# DC-DC_24V_To_5V0.net
KiCad netlist of a schematic drawn in Altium Designer
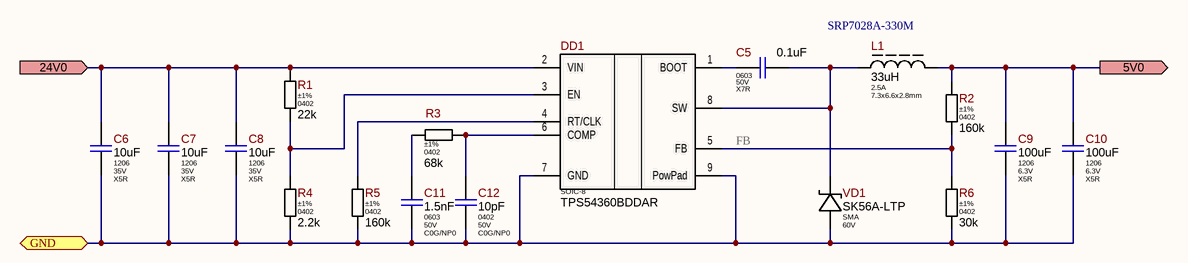
[diagram p0: DC-DC_24V_To_5V0.SchDoc]

(export (version "E")
  (design (tool "Eeschema 10.0.6"))
  (components
    (comp (ref "C5")
      (value "0.1uF")
      (footprint "C_CERAMIC_0603_MED")
      (description "100nF 50V X7R ±10% 0603 Ceramic Capacitor RoHS")
      (fields
        (field (name "PACKAGE") "0603")
        (field (name "VOLTAGE") "50V")
        (field (name "DIELECTRIC TYPE") "X7R")
        (field (name "PART NUMBER") "CL10B104KB8NNNC")
        (field (name "MANUFACTURER") "Samsung Electro-Mechanics")
      )
      (libsource (lib "EL.CVCM.T01") (part "Capacitor-NonPolar"))
    )
    (comp (ref "C6")
      (value "10uF")
      (footprint "CAP-1206(3216)X85T15")
      (description "10uF 35V X5R ±10% 1206 Ceramic Capacitor RoHS")
      (fields
        (field (name "PACKAGE") "1206")
        (field (name "VOLTAGE") "35V")
        (field (name "DIELECTRIC TYPE") "X5R")
        (field (name "PART NUMBER") "GRM319R6YA106KA12D")
        (field (name "MANUFACTURER") "Murata Electronics")
      )
      (libsource (lib "EL.CVCM.T01") (part "Capacitor-NonPolar"))
    )
    (comp (ref "C7")
      (value "10uF")
      (footprint "CAP-1206(3216)X85T15")
      (description "10uF 35V X5R ±10% 1206 Ceramic Capacitor RoHS")
      (fields
        (field (name "PACKAGE") "1206")
        (field (name "VOLTAGE") "35V")
        (field (name "DIELECTRIC TYPE") "X5R")
        (field (name "PART NUMBER") "GRM319R6YA106KA12D")
        (field (name "MANUFACTURER") "Murata Electronics")
      )
      (libsource (lib "EL.CVCM.T01") (part "Capacitor-NonPolar"))
    )
    (comp (ref "C8")
      (value "10uF")
      (footprint "CAP-1206(3216)X85T15")
      (description "10uF 35V X5R ±10% 1206 Ceramic Capacitor RoHS")
      (fields
        (field (name "PACKAGE") "1206")
        (field (name "VOLTAGE") "35V")
        (field (name "DIELECTRIC TYPE") "X5R")
        (field (name "PART NUMBER") "GRM319R6YA106KA12D")
        (field (name "MANUFACTURER") "Murata Electronics")
      )
      (libsource (lib "EL.CVCM.T01") (part "Capacitor-NonPolar"))
    )
    (comp (ref "C9")
      (value "100uF")
      (footprint "C_CERAMIC_1206_MED")
      (description "100uF 6.3V X5R ±20% 1206 Ceramic Capacitor RoHS")
      (fields
        (field (name "PACKAGE") "1206")
        (field (name "VOLTAGE") "6.3V")
        (field (name "DIELECTRIC TYPE") "X5R")
        (field (name "PART NUMBER") "CL31A107MQHNNNE")
        (field (name "MANUFACTURER") "Samsung Electro-Mechanics")
      )
      (libsource (lib "EL.CVCM.T01") (part "Capacitor-NonPolar"))
    )
    (comp (ref "C10")
      (value "100uF")
      (footprint "C_CERAMIC_1206_MED")
      (description "100uF 6.3V X5R ±20% 1206 Ceramic Capacitor RoHS")
      (fields
        (field (name "PACKAGE") "1206")
        (field (name "VOLTAGE") "6.3V")
        (field (name "DIELECTRIC TYPE") "X5R")
        (field (name "PART NUMBER") "CL31A107MQHNNNE")
        (field (name "MANUFACTURER") "Samsung Electro-Mechanics")
      )
      (libsource (lib "EL.CVCM.T01") (part "Capacitor-NonPolar"))
    )
    (comp (ref "C11")
      (value "1.5nF")
      (footprint "C_CERAMIC_0603_MED")
      (description "1.5nF 50V C0G(NP0) ±5% 0603 Ceramic Capacitor RoHS")
      (fields
        (field (name "PACKAGE") "0603")
        (field (name "VOLTAGE") "50V")
        (field (name "DIELECTRIC TYPE") "C0G/NP0")
        (field (name "PART NUMBER") "GRM1885C1H152JA01D")
        (field (name "MANUFACTURER") "Murata Electronics")
      )
      (libsource (lib "EL.CVCM.T01") (part "Capacitor-NonPolar"))
    )
    (comp (ref "C12")
      (value "10pF")
      (footprint "C_CERAMIC_0402_MED")
      (description "10pF 50V C0G ±5% 0402 Ceramic Capacitor RoHS")
      (fields
        (field (name "PACKAGE") "0402")
        (field (name "VOLTAGE") "50V")
        (field (name "DIELECTRIC TYPE") "C0G/NP0")
        (field (name "PART NUMBER") "CL05C100JB5NNNC")
        (field (name "MANUFACTURER") "Samsung Electro-Mechanics")
      )
      (libsource (lib "EL.CVCM.T01") (part "Capacitor-NonPolar"))
    )
    (comp (ref "DD1")
      (value "TPS54360BDDAR")
      (footprint "SOIC127P620X170_HS-9N")
      (description "60V Input, 3.5A, Step-Down DC/DC Converter With Eco-Mode, SOIC-8 EP")
      (fields
        (field (name "PACKAGE") "SOIC-8")
        (field (name "PART NUMBER") "TPS54360BDDAR")
        (field (name "MANUFACTURER") "Texas Instruments")
      )
      (libsource (lib "EL.CVCM.T01") (part "TPS54360B"))
    )
    (comp (ref "L1")
      (value "33uH")
      (footprint "SRP7028A-Series")
      (description "33uH Shielded Wirewound Power Inductor 2.5A 240mOhm Max")
      (fields
        (field (name "CURRENT") "2.5A")
        (field (name "PACKAGE") "7.3x6.6x2.8mm")
        (field (name "PART NUMBER") "SRP7028A-330M")
        (field (name "TOLERANCE") "±20%")
        (field (name "MANUFACTURER") "Bourns Inc")
      )
      (libsource (lib "EL.CVCM.T01") (part "Inductor-Ferrite-Fixed"))
    )
    (comp (ref "R1")
      (value "22k")
      (footprint "R_ANY_CHIP_0402_MED")
      (description "22 kOhms ±1% 1/16W 0402 Thick Film Resistor")
      (fields
        (field (name "TOLERANCE") "±1%")
        (field (name "PACKAGE") "0402")
        (field (name "PART NUMBER") "RC0402FR-0722KL")
        (field (name "MANUFACTURER") "Yageo")
      )
      (libsource (lib "EL.CVCM.T01") (part "Resistor"))
    )
    (comp (ref "R2")
      (value "160k")
      (footprint "R_ANY_CHIP_0402_MED")
      (description "160 kOhms ±1% 1/16W 0402 Thick Film Resistor")
      (fields
        (field (name "TOLERANCE") "±1%")
        (field (name "PACKAGE") "0402")
        (field (name "PART NUMBER") "RC0402FR-07160KL")
        (field (name "MANUFACTURER") "Yageo")
      )
      (libsource (lib "EL.CVCM.T01") (part "Resistor"))
    )
    (comp (ref "R3")
      (value "68k")
      (footprint "R_ANY_CHIP_0402_MED")
      (description "68 kOhms ±1% 1/16W 0402 Thick Film Resistor")
      (fields
        (field (name "TOLERANCE") "±1%")
        (field (name "PACKAGE") "0402")
        (field (name "PART NUMBER") "RC0402FR-0768KL")
        (field (name "MANUFACTURER") "Yageo")
      )
      (libsource (lib "EL.CVCM.T01") (part "Resistor"))
    )
    (comp (ref "R4")
      (value "2.2k")
      (footprint "R_ANY_CHIP_0402_MED")
      (description "2.2 kOhms ±1% 1/16W 0402 Thick Film Resistor")
      (fields
        (field (name "TOLERANCE") "±1%")
        (field (name "PACKAGE") "0402")
        (field (name "PART NUMBER") "RC0402FR-072K2L")
        (field (name "MANUFACTURER") "Yageo")
      )
      (libsource (lib "EL.CVCM.T01") (part "Resistor"))
    )
    (comp (ref "R5")
      (value "160k")
      (footprint "R_ANY_CHIP_0402_MED")
      (description "160 kOhms ±1% 1/16W 0402 Thick Film Resistor")
      (fields
        (field (name "TOLERANCE") "±1%")
        (field (name "PACKAGE") "0402")
        (field (name "PART NUMBER") "RC0402FR-07160KL")
        (field (name "MANUFACTURER") "Yageo")
      )
      (libsource (lib "EL.CVCM.T01") (part "Resistor"))
    )
    (comp (ref "R6")
      (value "30k")
      (footprint "R_ANY_CHIP_0402_MED")
      (description "30 kOhms ±1% 1/16W 0402 Thick Film Resistor")
      (fields
        (field (name "TOLERANCE") "±1%")
        (field (name "PACKAGE") "0402")
        (field (name "PART NUMBER") "RC0402FR-0730KL")
        (field (name "MANUFACTURER") "Yageo")
      )
      (libsource (lib "EL.CVCM.T01") (part "Resistor"))
    )
    (comp (ref "VD1")
      (value "SK56A-LTP")
      (footprint "SMA_MED")
      (description "Diode Schottky 60V 5A, SMA")
      (fields
        (field (name "PART NUMBER") "SK56A-LTP")
        (field (name "PACKAGE") "SMA")
        (field (name "VOLTAGE") "60V")
        (field (name "MANUFACTURER") "Micro Commercial Components")
      )
      (libsource (lib "EL.CVCM.T01") (part "Diode-Schottky"))
    )
  )
  (nets
    (net (code "1") (name "/5V0") (class "Default")
      (node (ref "C10") (pin "1") (pinfunction "1_1") (pintype "passive"))
      (node (ref "C9") (pin "1") (pinfunction "1_1") (pintype "passive"))
      (node (ref "L1") (pin "2") (pintype "passive"))
      (node (ref "R2") (pin "1") (pintype "passive"))
    )
    (net (code "2") (name "/24V0") (class "Default")
      (node (ref "C6") (pin "1") (pinfunction "1_1") (pintype "passive"))
      (node (ref "C7") (pin "1") (pinfunction "1_1") (pintype "passive"))
      (node (ref "C8") (pin "1") (pinfunction "1_1") (pintype "passive"))
      (node (ref "DD1") (pin "2") (pinfunction "VIN_2") (pintype "passive"))
      (node (ref "R1") (pin "1") (pintype "passive"))
    )
    (net (code "3") (name "/FB") (class "Default")
      (node (ref "DD1") (pin "5") (pinfunction "FB_5") (pintype "passive"))
      (node (ref "R2") (pin "2") (pintype "passive"))
      (node (ref "R6") (pin "1") (pintype "passive"))
    )
    (net (code "4") (name "/GND") (class "Default")
      (node (ref "C10") (pin "2") (pinfunction "2_2") (pintype "passive"))
      (node (ref "C11") (pin "1") (pinfunction "1_1") (pintype "passive"))
      (node (ref "C12") (pin "2") (pinfunction "2_2") (pintype "passive"))
      (node (ref "C6") (pin "2") (pinfunction "2_2") (pintype "passive"))
      (node (ref "C7") (pin "2") (pinfunction "2_2") (pintype "passive"))
      (node (ref "C8") (pin "2") (pinfunction "2_2") (pintype "passive"))
      (node (ref "C9") (pin "2") (pinfunction "2_2") (pintype "passive"))
      (node (ref "DD1") (pin "7") (pinfunction "GND_7") (pintype "passive"))
      (node (ref "DD1") (pin "9") (pinfunction "PowPad_9") (pintype "passive"))
      (node (ref "R4") (pin "2") (pintype "passive"))
      (node (ref "R5") (pin "2") (pintype "passive"))
      (node (ref "R6") (pin "2") (pintype "passive"))
      (node (ref "VD1") (pin "AN") (pintype "passive"))
    )
    (net (code "5") (name "Net-(C11-Pad2)") (class "Default")
      (node (ref "C11") (pin "2") (pinfunction "2_2") (pintype "passive"))
      (node (ref "R3") (pin "2") (pintype "passive"))
    )
    (net (code "6") (name "Net-(DD1-BOOT)") (class "Default")
      (node (ref "C5") (pin "1") (pinfunction "1_1") (pintype "passive"))
      (node (ref "DD1") (pin "1") (pinfunction "BOOT_1") (pintype "passive"))
    )
    (net (code "7") (name "Net-(DD1-COMP)") (class "Default")
      (node (ref "C12") (pin "1") (pinfunction "1_1") (pintype "passive"))
      (node (ref "DD1") (pin "6") (pinfunction "COMP_6") (pintype "passive"))
      (node (ref "R3") (pin "1") (pintype "passive"))
    )
    (net (code "8") (name "Net-(DD1-EN)") (class "Default")
      (node (ref "DD1") (pin "3") (pinfunction "EN_3") (pintype "passive"))
      (node (ref "R1") (pin "2") (pintype "passive"))
      (node (ref "R4") (pin "1") (pintype "passive"))
    )
    (net (code "9") (name "Net-(DD1-RT{slash}CLK)") (class "Default")
      (node (ref "DD1") (pin "4") (pinfunction "RT/CLK_4") (pintype "passive"))
      (node (ref "R5") (pin "1") (pintype "passive"))
    )
    (net (code "10") (name "Net-(DD1-SW)") (class "Default")
      (node (ref "C5") (pin "2") (pinfunction "2_2") (pintype "passive"))
      (node (ref "DD1") (pin "8") (pinfunction "SW_8") (pintype "passive"))
      (node (ref "L1") (pin "1") (pintype "passive"))
      (node (ref "VD1") (pin "CA") (pintype "passive"))
    )
  )
)
